# LTC6803.net
KiCad netlist of a schematic drawn in Altium Designer
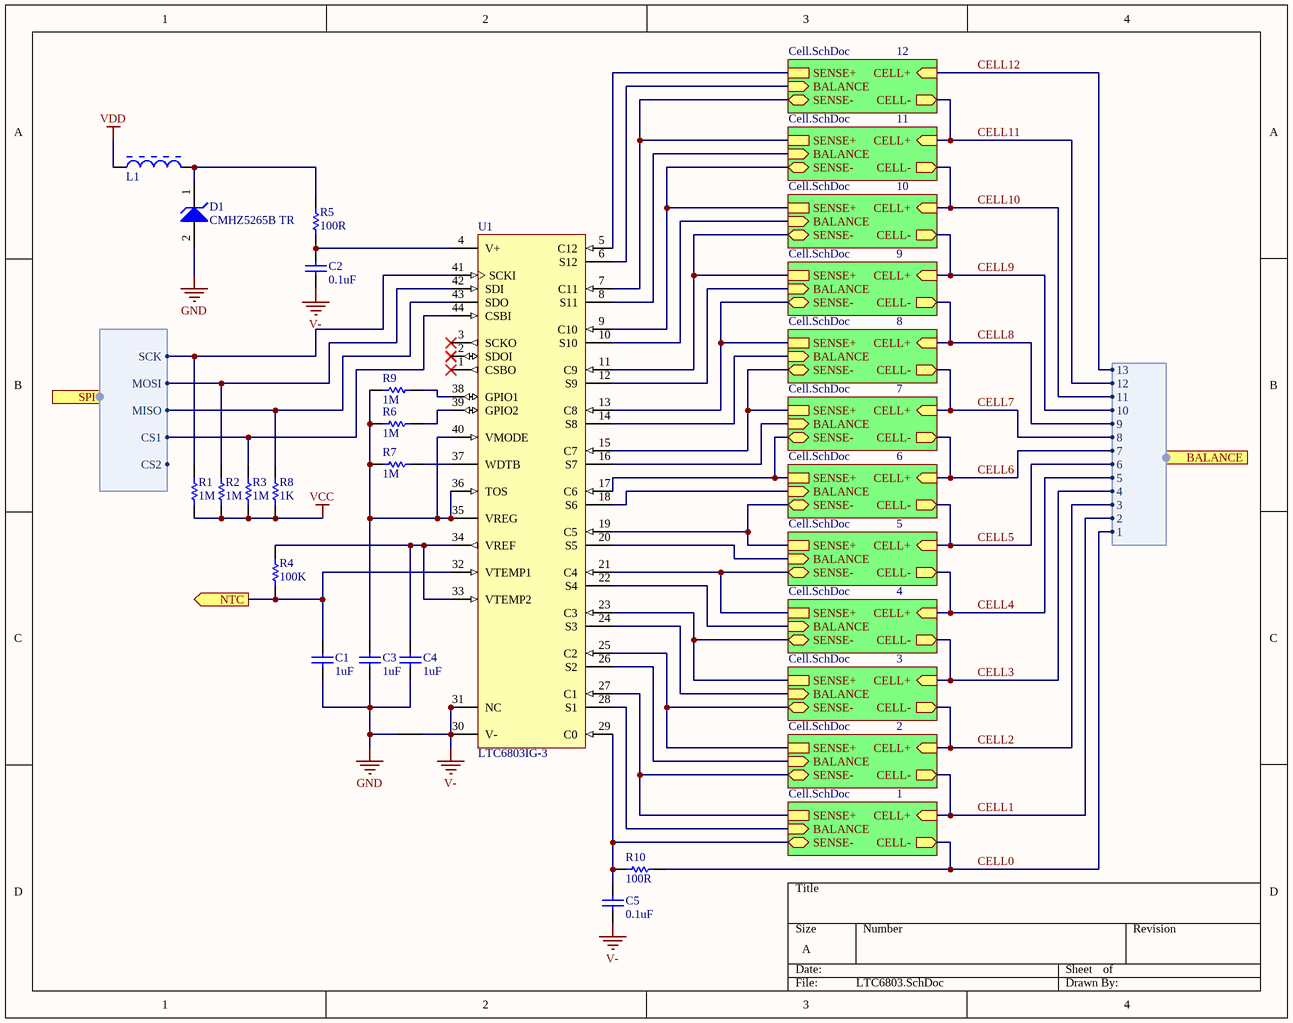
[diagram p0: LTC6803.SchDoc]

(export (version "E")
  (design (tool "Eeschema 10.0.6"))
  (components
    (comp (ref "*") (value "NetTie") (footprint "NetTie") (libsource (lib "Components") (part "NetTie")))
    (comp (ref "C1")
      (value "1uF")
      (footprint "C0402[1005X55]")
      (description "1uF 6.3V 10% 0402 (1005 Metric)")
      (fields (field (name "TOLERANCE") "10%") (field (name "PARTNUMBER") "GRM155R70J105KA12D"))
      (libsource (lib "Capacitors") (part "CAP_1uF_6.3V_0402_10%"))
    )
    (comp (ref "C2")
      (value "0.1uF")
      (footprint "C0402[1005X55]")
      (description "0.1uF 100V 10% 0402 (1005 Metric)")
      (fields (field (name "TOLERANCE") "10%") (field (name "PARTNUMBER") "GRM155R62A104KE14D"))
      (libsource (lib "Capacitors") (part "CAP_0.1uF_100V_0402_10%"))
    )
    (comp (ref "C3")
      (value "1uF")
      (footprint "C0402[1005X55]")
      (description "1uF 6.3V 10% 0402 (1005 Metric)")
      (fields (field (name "TOLERANCE") "10%") (field (name "PARTNUMBER") "GRM155R70J105KA12D"))
      (libsource (lib "Capacitors") (part "CAP_1uF_6.3V_0402_10%"))
    )
    (comp (ref "C4")
      (value "1uF")
      (footprint "C0402[1005X55]")
      (description "1uF 6.3V 10% 0402 (1005 Metric)")
      (fields (field (name "TOLERANCE") "10%") (field (name "PARTNUMBER") "GRM155R70J105KA12D"))
      (libsource (lib "Capacitors") (part "CAP_1uF_6.3V_0402_10%"))
    )
    (comp (ref "C5")
      (value "0.1uF")
      (footprint "C0402[1005X55]")
      (description "0.1uF 6.3V 10% 0402 (1005 Metric)")
      (fields (field (name "TOLERANCE") "10%") (field (name "PARTNUMBER") "GRM155R70J104KA01D"))
      (libsource (lib "Capacitors") (part "CAP_0.1uF_6.3V_0402_10%"))
    )
    (comp (ref "D1")
      (value "CMHZ5265B TR")
      (footprint "SOD-123")
      (description "Zener Diodes 500mW Zener Diode 185mA 58.9V to 2V")
      (fields (field (name "MANUFACTURER") "Central Semiconductor"))
      (libsource (lib "Diodes") (part "CMHZ5265B"))
    )
    (comp (ref "L1")
      (value "MURA-FB-2")
      (footprint "MURA-BLM31-B60-CHIP-2_V3")
      (description "EMI Filter Beads, Chips & Arrays 1206 33 OHM")
      (fields (field (name "PARTNUMBER") "BLM31PG330SN1L") (field (name "MANUFACTURER") "Murata"))
      (libsource (lib "Components") (part "MURA-FB-2"))
    )
    (comp (ref "R1")
      (value "1M")
      (footprint "R0402[1005]")
      (description "1M 0.063W 1% 0402 (1005 Metric)")
      (fields (field (name "POWER") "0.063W") (field (name "TOLERANCE") "1%"))
      (libsource (lib "Resistors") (part "RES_1M_0402_1%"))
    )
    (comp (ref "R2")
      (value "1M")
      (footprint "R0402[1005]")
      (description "1M 0.063W 1% 0402 (1005 Metric)")
      (fields (field (name "POWER") "0.063W") (field (name "TOLERANCE") "1%"))
      (libsource (lib "Resistors") (part "RES_1M_0402_1%"))
    )
    (comp (ref "R3")
      (value "1M")
      (footprint "R0402[1005]")
      (description "1M 0.063W 1% 0402 (1005 Metric)")
      (fields (field (name "POWER") "0.063W") (field (name "TOLERANCE") "1%"))
      (libsource (lib "Resistors") (part "RES_1M_0402_1%"))
    )
    (comp (ref "R4")
      (value "100K")
      (footprint "R0402[1005]")
      (description "100K 0.063W 1% 0402 (1005 Metric)")
      (fields (field (name "POWER") "0.063W") (field (name "TOLERANCE") "1%"))
      (libsource (lib "Resistors") (part "RES_100K_0402_1%"))
    )
    (comp (ref "R5")
      (value "100R")
      (footprint "R0402[1005]")
      (description "100R 0.063W 1% 0402 (1005 Metric)")
      (fields (field (name "POWER") "0.063W") (field (name "TOLERANCE") "1%"))
      (libsource (lib "Resistors") (part "RES_100R_0402_1%"))
    )
    (comp (ref "R6")
      (value "1M")
      (footprint "R0402[1005]")
      (description "1M 0.063W 1% 0402 (1005 Metric)")
      (fields (field (name "POWER") "0.063W") (field (name "TOLERANCE") "1%"))
      (libsource (lib "Resistors") (part "RES_1M_0402_1%"))
    )
    (comp (ref "R7")
      (value "1M")
      (footprint "R0402[1005]")
      (description "1M 0.063W 1% 0402 (1005 Metric)")
      (fields (field (name "POWER") "0.063W") (field (name "TOLERANCE") "1%"))
      (libsource (lib "Resistors") (part "RES_1M_0402_1%"))
    )
    (comp (ref "R8")
      (value "1K")
      (footprint "R0402[1005]")
      (description "1K 0.063W 1% 0402 (1005 Metric)")
      (fields (field (name "MANUFACTURER") "KOA Speer") (field (name "PARTNUMBER") "RK73H1ETTP1001F"))
      (libsource (lib "Resistors") (part "RES_1K_0402_1%"))
    )
    (comp (ref "R9")
      (value "1M")
      (footprint "R0402[1005]")
      (description "1M 0.063W 1% 0402 (1005 Metric)")
      (fields (field (name "POWER") "0.063W") (field (name "TOLERANCE") "1%"))
      (libsource (lib "Resistors") (part "RES_1M_0402_1%"))
    )
    (comp (ref "R10")
      (value "100R")
      (footprint "R0402[1005]")
      (description "100R 0.063W 1% 0402 (1005 Metric)")
      (fields (field (name "POWER") "0.063W") (field (name "TOLERANCE") "1%"))
      (libsource (lib "Resistors") (part "RES_100R_0402_1%"))
    )
    (comp (ref "U1")
      (value "LTC6803IG-3")
      (footprint "TSSOP-44")
      (fields (field (name "PARTNUMBER") "LTC6803IG-3#PBF") (field (name "MANUFACTURER") "Linear Technology"))
      (libsource (lib "ICs") (part "LTC6803IG-3"))
    )
  )
  (nets
    (net (code "3") (name "/BALANCE") (class "Default")
      (node (ref "U1") (pin "28") (pinfunction "S1_28") (pintype "tri_state"))
    )
    (net (code "4") (name "/BALANCE_1") (class "Default")
      (node (ref "U1") (pin "6") (pinfunction "S12_6") (pintype "tri_state"))
    )
    (net (code "5") (name "/BALANCE_2") (class "Default")
      (node (ref "U1") (pin "8") (pinfunction "S11_8") (pintype "tri_state"))
    )
    (net (code "6") (name "/BALANCE_3") (class "Default")
      (node (ref "U1") (pin "10") (pinfunction "S10_10") (pintype "tri_state"))
    )
    (net (code "7") (name "/BALANCE_4") (class "Default")
      (node (ref "U1") (pin "12") (pinfunction "S9_12") (pintype "tri_state"))
    )
    (net (code "8") (name "/BALANCE_5") (class "Default")
      (node (ref "U1") (pin "14") (pinfunction "S8_14") (pintype "tri_state"))
    )
    (net (code "9") (name "/BALANCE_6") (class "Default")
      (node (ref "U1") (pin "16") (pinfunction "S7_16") (pintype "tri_state"))
    )
    (net (code "10") (name "/BALANCE_7") (class "Default")
      (node (ref "U1") (pin "18") (pinfunction "S6_18") (pintype "tri_state"))
    )
    (net (code "11") (name "/BALANCE_8") (class "Default")
      (node (ref "U1") (pin "20") (pinfunction "S5_20") (pintype "tri_state"))
    )
    (net (code "12") (name "/BALANCE_9") (class "Default")
      (node (ref "U1") (pin "22") (pinfunction "S4_22") (pintype "tri_state"))
    )
    (net (code "13") (name "/BALANCE_10") (class "Default")
      (node (ref "U1") (pin "24") (pinfunction "S3_24") (pintype "tri_state"))
    )
    (net (code "14") (name "/BALANCE_11") (class "Default")
      (node (ref "U1") (pin "26") (pinfunction "S2_26") (pintype "tri_state"))
    )
    (net (code "15") (name "/CELL0") (class "Default")
      (node (ref "R10") (pin "2") (pinfunction "2_2") (pintype "passive"))
    )
    (net (code "28") (name "/NTC") (class "Default")
      (node (ref "C1") (pin "2") (pinfunction "2_2") (pintype "passive"))
      (node (ref "R4") (pin "1") (pinfunction "1_1") (pintype "passive"))
      (node (ref "U1") (pin "32") (pinfunction "VTEMP1_32") (pintype "input"))
    )
    (net (code "29") (name "/SENSE+") (class "Default")
      (node (ref "U1") (pin "27") (pinfunction "C1_27") (pintype "input"))
    )
    (net (code "30") (name "/SENSE+_1") (class "Default")
      (node (ref "U1") (pin "5") (pinfunction "C12_5") (pintype "input"))
    )
    (net (code "31") (name "/SENSE+_2") (class "Default")
      (node (ref "U1") (pin "7") (pinfunction "C11_7") (pintype "input"))
    )
    (net (code "32") (name "/SENSE+_3") (class "Default")
      (node (ref "U1") (pin "9") (pinfunction "C10_9") (pintype "input"))
    )
    (net (code "33") (name "/SENSE+_4") (class "Default")
      (node (ref "U1") (pin "11") (pinfunction "C9_11") (pintype "input"))
    )
    (net (code "34") (name "/SENSE+_5") (class "Default")
      (node (ref "U1") (pin "13") (pinfunction "C8_13") (pintype "input"))
    )
    (net (code "35") (name "/SENSE+_6") (class "Default")
      (node (ref "U1") (pin "15") (pinfunction "C7_15") (pintype "input"))
    )
    (net (code "36") (name "/SENSE+_7") (class "Default")
      (node (ref "U1") (pin "17") (pinfunction "C6_17") (pintype "input"))
    )
    (net (code "37") (name "/SENSE+_8") (class "Default")
      (node (ref "U1") (pin "19") (pinfunction "C5_19") (pintype "input"))
    )
    (net (code "38") (name "/SENSE+_9") (class "Default")
      (node (ref "U1") (pin "21") (pinfunction "C4_21") (pintype "input"))
    )
    (net (code "39") (name "/SENSE+_10") (class "Default")
      (node (ref "U1") (pin "23") (pinfunction "C3_23") (pintype "input"))
    )
    (net (code "40") (name "/SENSE+_11") (class "Default")
      (node (ref "U1") (pin "25") (pinfunction "C2_25") (pintype "input"))
    )
    (net (code "41") (name "/SENSE-") (class "Default")
      (node (ref "C5") (pin "2") (pinfunction "2_2") (pintype "passive"))
      (node (ref "R10") (pin "1") (pinfunction "1_1") (pintype "passive"))
      (node (ref "U1") (pin "29") (pinfunction "C0_29") (pintype "input"))
    )
    (net (code "44") (name "GND") (class "Default")
      (node (ref "*") (pin "1") (pinfunction "1_1") (pintype "passive"))
      (node (ref "C1") (pin "1") (pinfunction "1_1") (pintype "passive"))
      (node (ref "C3") (pin "1") (pinfunction "1_1") (pintype "passive"))
      (node (ref "C4") (pin "1") (pinfunction "1_1") (pintype "passive"))
      (node (ref "D1") (pin "2") (pinfunction "A_2") (pintype "passive"))
    )
    (net (code "45") (name "Net-(D1-K)") (class "Default")
      (node (ref "D1") (pin "1") (pinfunction "K_1") (pintype "passive"))
      (node (ref "L1") (pin "2") (pinfunction "2_2") (pintype "passive"))
      (node (ref "R5") (pin "2") (pinfunction "2_2") (pintype "passive"))
    )
    (net (code "46") (name "Net-(U1-CSBI)") (class "Default")
      (node (ref "R3") (pin "2") (pinfunction "2_2") (pintype "passive"))
      (node (ref "U1") (pin "44") (pinfunction "CSBI_44") (pintype "input"))
    )
    (net (code "47") (name "Net-(U1-GPIO1)") (class "Default")
      (node (ref "R9") (pin "1") (pinfunction "1_1") (pintype "passive"))
      (node (ref "U1") (pin "38") (pinfunction "GPIO1_38") (pintype "bidirectional"))
    )
    (net (code "48") (name "Net-(U1-GPIO2)") (class "Default")
      (node (ref "R6") (pin "1") (pinfunction "1_1") (pintype "passive"))
      (node (ref "U1") (pin "39") (pinfunction "GPIO2_39") (pintype "bidirectional"))
    )
    (net (code "49") (name "Net-(U1-SCKI)") (class "Default")
      (node (ref "R1") (pin "2") (pinfunction "2_2") (pintype "passive"))
      (node (ref "U1") (pin "41") (pinfunction "SCKI_41") (pintype "input"))
    )
    (net (code "50") (name "Net-(U1-SDI)") (class "Default")
      (node (ref "R2") (pin "2") (pinfunction "2_2") (pintype "passive"))
      (node (ref "U1") (pin "42") (pinfunction "SDI_42") (pintype "input"))
    )
    (net (code "51") (name "Net-(U1-SDO)") (class "Default")
      (node (ref "R8") (pin "1") (pinfunction "1_1") (pintype "passive"))
      (node (ref "U1") (pin "43") (pinfunction "SDO_43") (pintype "open_collector"))
    )
    (net (code "52") (name "Net-(U1-TOS)") (class "Default")
      (node (ref "C3") (pin "2") (pinfunction "2_2") (pintype "passive"))
      (node (ref "R6") (pin "2") (pinfunction "2_2") (pintype "passive"))
      (node (ref "R7") (pin "2") (pinfunction "2_2") (pintype "passive"))
      (node (ref "R9") (pin "2") (pinfunction "2_2") (pintype "passive"))
      (node (ref "U1") (pin "35") (pinfunction "VREG_35") (pintype "power_in"))
      (node (ref "U1") (pin "36") (pinfunction "TOS_36") (pintype "input"))
      (node (ref "U1") (pin "40") (pinfunction "VMODE_40") (pintype "input"))
    )
    (net (code "53") (name "Net-(U1-V+)") (class "Default")
      (node (ref "C2") (pin "2") (pinfunction "2_2") (pintype "passive"))
      (node (ref "R5") (pin "1") (pinfunction "1_1") (pintype "passive"))
      (node (ref "U1") (pin "4") (pinfunction "V+_4") (pintype "power_in"))
    )
    (net (code "54") (name "Net-(U1-VREF)") (class "Default")
      (node (ref "C4") (pin "2") (pinfunction "2_2") (pintype "passive"))
      (node (ref "R4") (pin "2") (pinfunction "2_2") (pintype "passive"))
      (node (ref "U1") (pin "33") (pinfunction "VTEMP2_33") (pintype "input"))
      (node (ref "U1") (pin "34") (pinfunction "VREF_34") (pintype "output"))
    )
    (net (code "55") (name "Net-(U1-WDTB)") (class "Default")
      (node (ref "R7") (pin "1") (pinfunction "1_1") (pintype "passive"))
      (node (ref "U1") (pin "37") (pinfunction "WDTB_37") (pintype "open_collector"))
    )
    (net (code "56") (name "V-") (class "Default")
      (node (ref "*") (pin "2") (pinfunction "2_2") (pintype "passive"))
      (node (ref "C2") (pin "1") (pinfunction "1_1") (pintype "passive"))
      (node (ref "C5") (pin "1") (pinfunction "1_1") (pintype "passive"))
      (node (ref "U1") (pin "30") (pinfunction "V-_30") (pintype "power_in"))
      (node (ref "U1") (pin "31") (pinfunction "NC_31") (pintype "passive"))
    )
    (net (code "57") (name "VCC") (class "Default")
      (node (ref "R1") (pin "1") (pinfunction "1_1") (pintype "passive"))
      (node (ref "R2") (pin "1") (pinfunction "1_1") (pintype "passive"))
      (node (ref "R3") (pin "1") (pinfunction "1_1") (pintype "passive"))
      (node (ref "R8") (pin "2") (pinfunction "2_2") (pintype "passive"))
    )
    (net (code "58") (name "VDD") (class "Default")
      (node (ref "L1") (pin "1") (pinfunction "1_1") (pintype "passive"))
    )
    (net (code "59") (name "unconnected-(U1-CSBO-Pad1)") (class "Default")
      (node (ref "U1") (pin "1") (pinfunction "CSBO_1") (pintype "output+no_connect"))
    )
    (net (code "60") (name "unconnected-(U1-SCKO-Pad3)") (class "Default")
      (node (ref "U1") (pin "3") (pinfunction "SCKO_3") (pintype "output+no_connect"))
    )
    (net (code "61") (name "unconnected-(U1-SDOI-Pad2)") (class "Default")
      (node (ref "U1") (pin "2") (pinfunction "SDOI_2") (pintype "bidirectional+no_connect"))
    )
  )
)
